# Rad_Sensor_EV_1.net
KiCad netlist of a schematic drawn in EAGLE
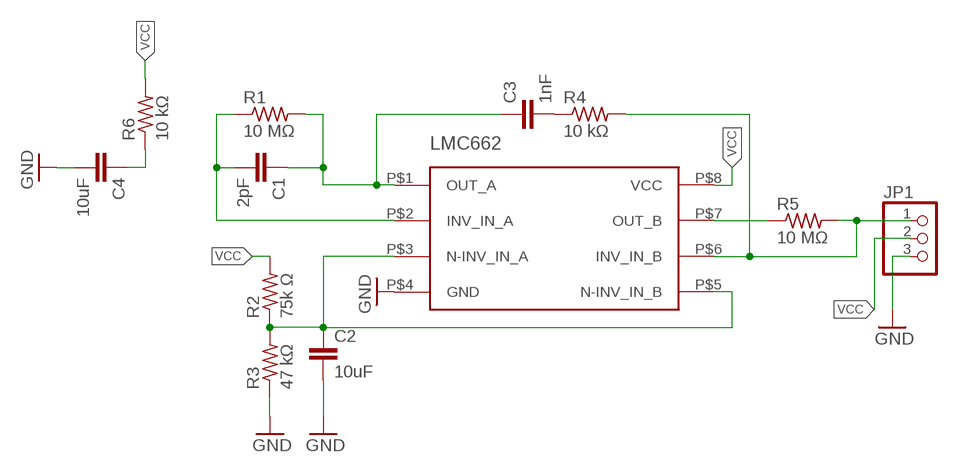
[diagram p0: schematic, sheet 1]

(export (version "E")
  (design (tool "Eeschema 10.0.6"))
  (components
    (comp (ref "C1")
      (value "2pF")
      (footprint "eagle-import:C0805")
      (libsource (lib "eagle-import") (part "C-EUC0805"))
    )
    (comp (ref "C2")
      (value "10uF")
      (footprint "eagle-import:C0805")
      (libsource (lib "eagle-import") (part "C-EUC0805"))
    )
    (comp (ref "C3")
      (value "1nF")
      (footprint "eagle-import:C0805")
      (libsource (lib "eagle-import") (part "C-EUC0805"))
    )
    (comp (ref "C4")
      (value "10uF")
      (footprint "eagle-import:C0805")
      (libsource (lib "eagle-import") (part "C-EUC0805"))
    )
    (comp (ref "JP1")
      (value "PINHD-1X3")
      (footprint "eagle-import:1X03")
      (libsource (lib "eagle-import") (part "PINHD-1X3"))
    )
    (comp (ref "R1")
      (value "10 MΩ")
      (footprint "eagle-import:R0805")
      (libsource (lib "eagle-import") (part "R-US_R0805"))
    )
    (comp (ref "R2")
      (value "75k Ω")
      (footprint "eagle-import:R0805")
      (libsource (lib "eagle-import") (part "R-US_R0805"))
    )
    (comp (ref "R3")
      (value "47 kΩ")
      (footprint "eagle-import:R0805")
      (libsource (lib "eagle-import") (part "R-US_R0805"))
    )
    (comp (ref "R4")
      (value "10 kΩ")
      (footprint "eagle-import:R0805")
      (libsource (lib "eagle-import") (part "R-US_R0805"))
    )
    (comp (ref "R5")
      (value "10 MΩ")
      (footprint "eagle-import:R0805")
      (libsource (lib "eagle-import") (part "R-US_R0805"))
    )
    (comp (ref "R6")
      (value "10 kΩ")
      (footprint "eagle-import:R0805")
      (libsource (lib "eagle-import") (part "R-US_R0805"))
    )
    (comp (ref "U$1")
      (value "LMC662")
      (footprint "eagle-import:LMC662")
      (libsource (lib "eagle-import") (part "LMC662"))
    )
  )
  (nets
    (net (code "1") (name "GND") (class "Default")
      (node (ref "C2") (pin "2") (pinfunction "2_2") (pintype "passive"))
      (node (ref "C4") (pin "2") (pinfunction "2_2") (pintype "passive"))
      (node (ref "JP1") (pin "3") (pinfunction "3_3") (pintype "passive"))
      (node (ref "R3") (pin "1") (pinfunction "1_1") (pintype "passive"))
      (node (ref "U$1") (pin "P$4") (pinfunction "GND_P$4") (pintype "bidirectional"))
    )
    (net (code "2") (name "Net-(C3-Pad2)") (class "Default")
      (node (ref "C3") (pin "2") (pinfunction "2_2") (pintype "passive"))
      (node (ref "R4") (pin "1") (pinfunction "1_1") (pintype "passive"))
    )
    (net (code "3") (name "Net-(C4-Pad1)") (class "Default")
      (node (ref "C4") (pin "1") (pinfunction "1_1") (pintype "passive"))
      (node (ref "R6") (pin "1") (pinfunction "1_1") (pintype "passive"))
    )
    (net (code "4") (name "Net-(U$1-INV_IN_A)") (class "Default")
      (node (ref "C1") (pin "2") (pinfunction "2_2") (pintype "passive"))
      (node (ref "R1") (pin "1") (pinfunction "1_1") (pintype "passive"))
      (node (ref "U$1") (pin "P$2") (pinfunction "INV_IN_A_P$2") (pintype "bidirectional"))
    )
    (net (code "5") (name "Net-(U$1-INV_IN_B)") (class "Default")
      (node (ref "JP1") (pin "1") (pinfunction "1_1") (pintype "passive"))
      (node (ref "R4") (pin "2") (pinfunction "2_2") (pintype "passive"))
      (node (ref "R5") (pin "2") (pinfunction "2_2") (pintype "passive"))
      (node (ref "U$1") (pin "P$6") (pinfunction "INV_IN_B_P$6") (pintype "bidirectional"))
    )
    (net (code "6") (name "Net-(U$1-N-INV_IN_A)") (class "Default")
      (node (ref "C2") (pin "1") (pinfunction "1_1") (pintype "passive"))
      (node (ref "R2") (pin "1") (pinfunction "1_1") (pintype "passive"))
      (node (ref "R3") (pin "2") (pinfunction "2_2") (pintype "passive"))
      (node (ref "U$1") (pin "P$3") (pinfunction "N-INV_IN_A_P$3") (pintype "bidirectional"))
      (node (ref "U$1") (pin "P$5") (pinfunction "N-INV_IN_B_P$5") (pintype "bidirectional"))
    )
    (net (code "7") (name "Net-(U$1-OUT_A)") (class "Default")
      (node (ref "C1") (pin "1") (pinfunction "1_1") (pintype "passive"))
      (node (ref "C3") (pin "1") (pinfunction "1_1") (pintype "passive"))
      (node (ref "R1") (pin "2") (pinfunction "2_2") (pintype "passive"))
      (node (ref "U$1") (pin "P$1") (pinfunction "OUT_A_P$1") (pintype "bidirectional"))
    )
    (net (code "8") (name "Net-(U$1-OUT_B)") (class "Default")
      (node (ref "R5") (pin "1") (pinfunction "1_1") (pintype "passive"))
      (node (ref "U$1") (pin "P$7") (pinfunction "OUT_B_P$7") (pintype "bidirectional"))
    )
    (net (code "9") (name "VCC") (class "Default")
      (node (ref "JP1") (pin "2") (pinfunction "2_2") (pintype "passive"))
      (node (ref "R2") (pin "2") (pinfunction "2_2") (pintype "passive"))
      (node (ref "R6") (pin "2") (pinfunction "2_2") (pintype "passive"))
      (node (ref "U$1") (pin "P$8") (pinfunction "VCC_P$8") (pintype "bidirectional"))
    )
  )
)
